# SCH_NFC-Card_2026-09-23.net
KiCad netlist of a schematic drawn in EasyEDA
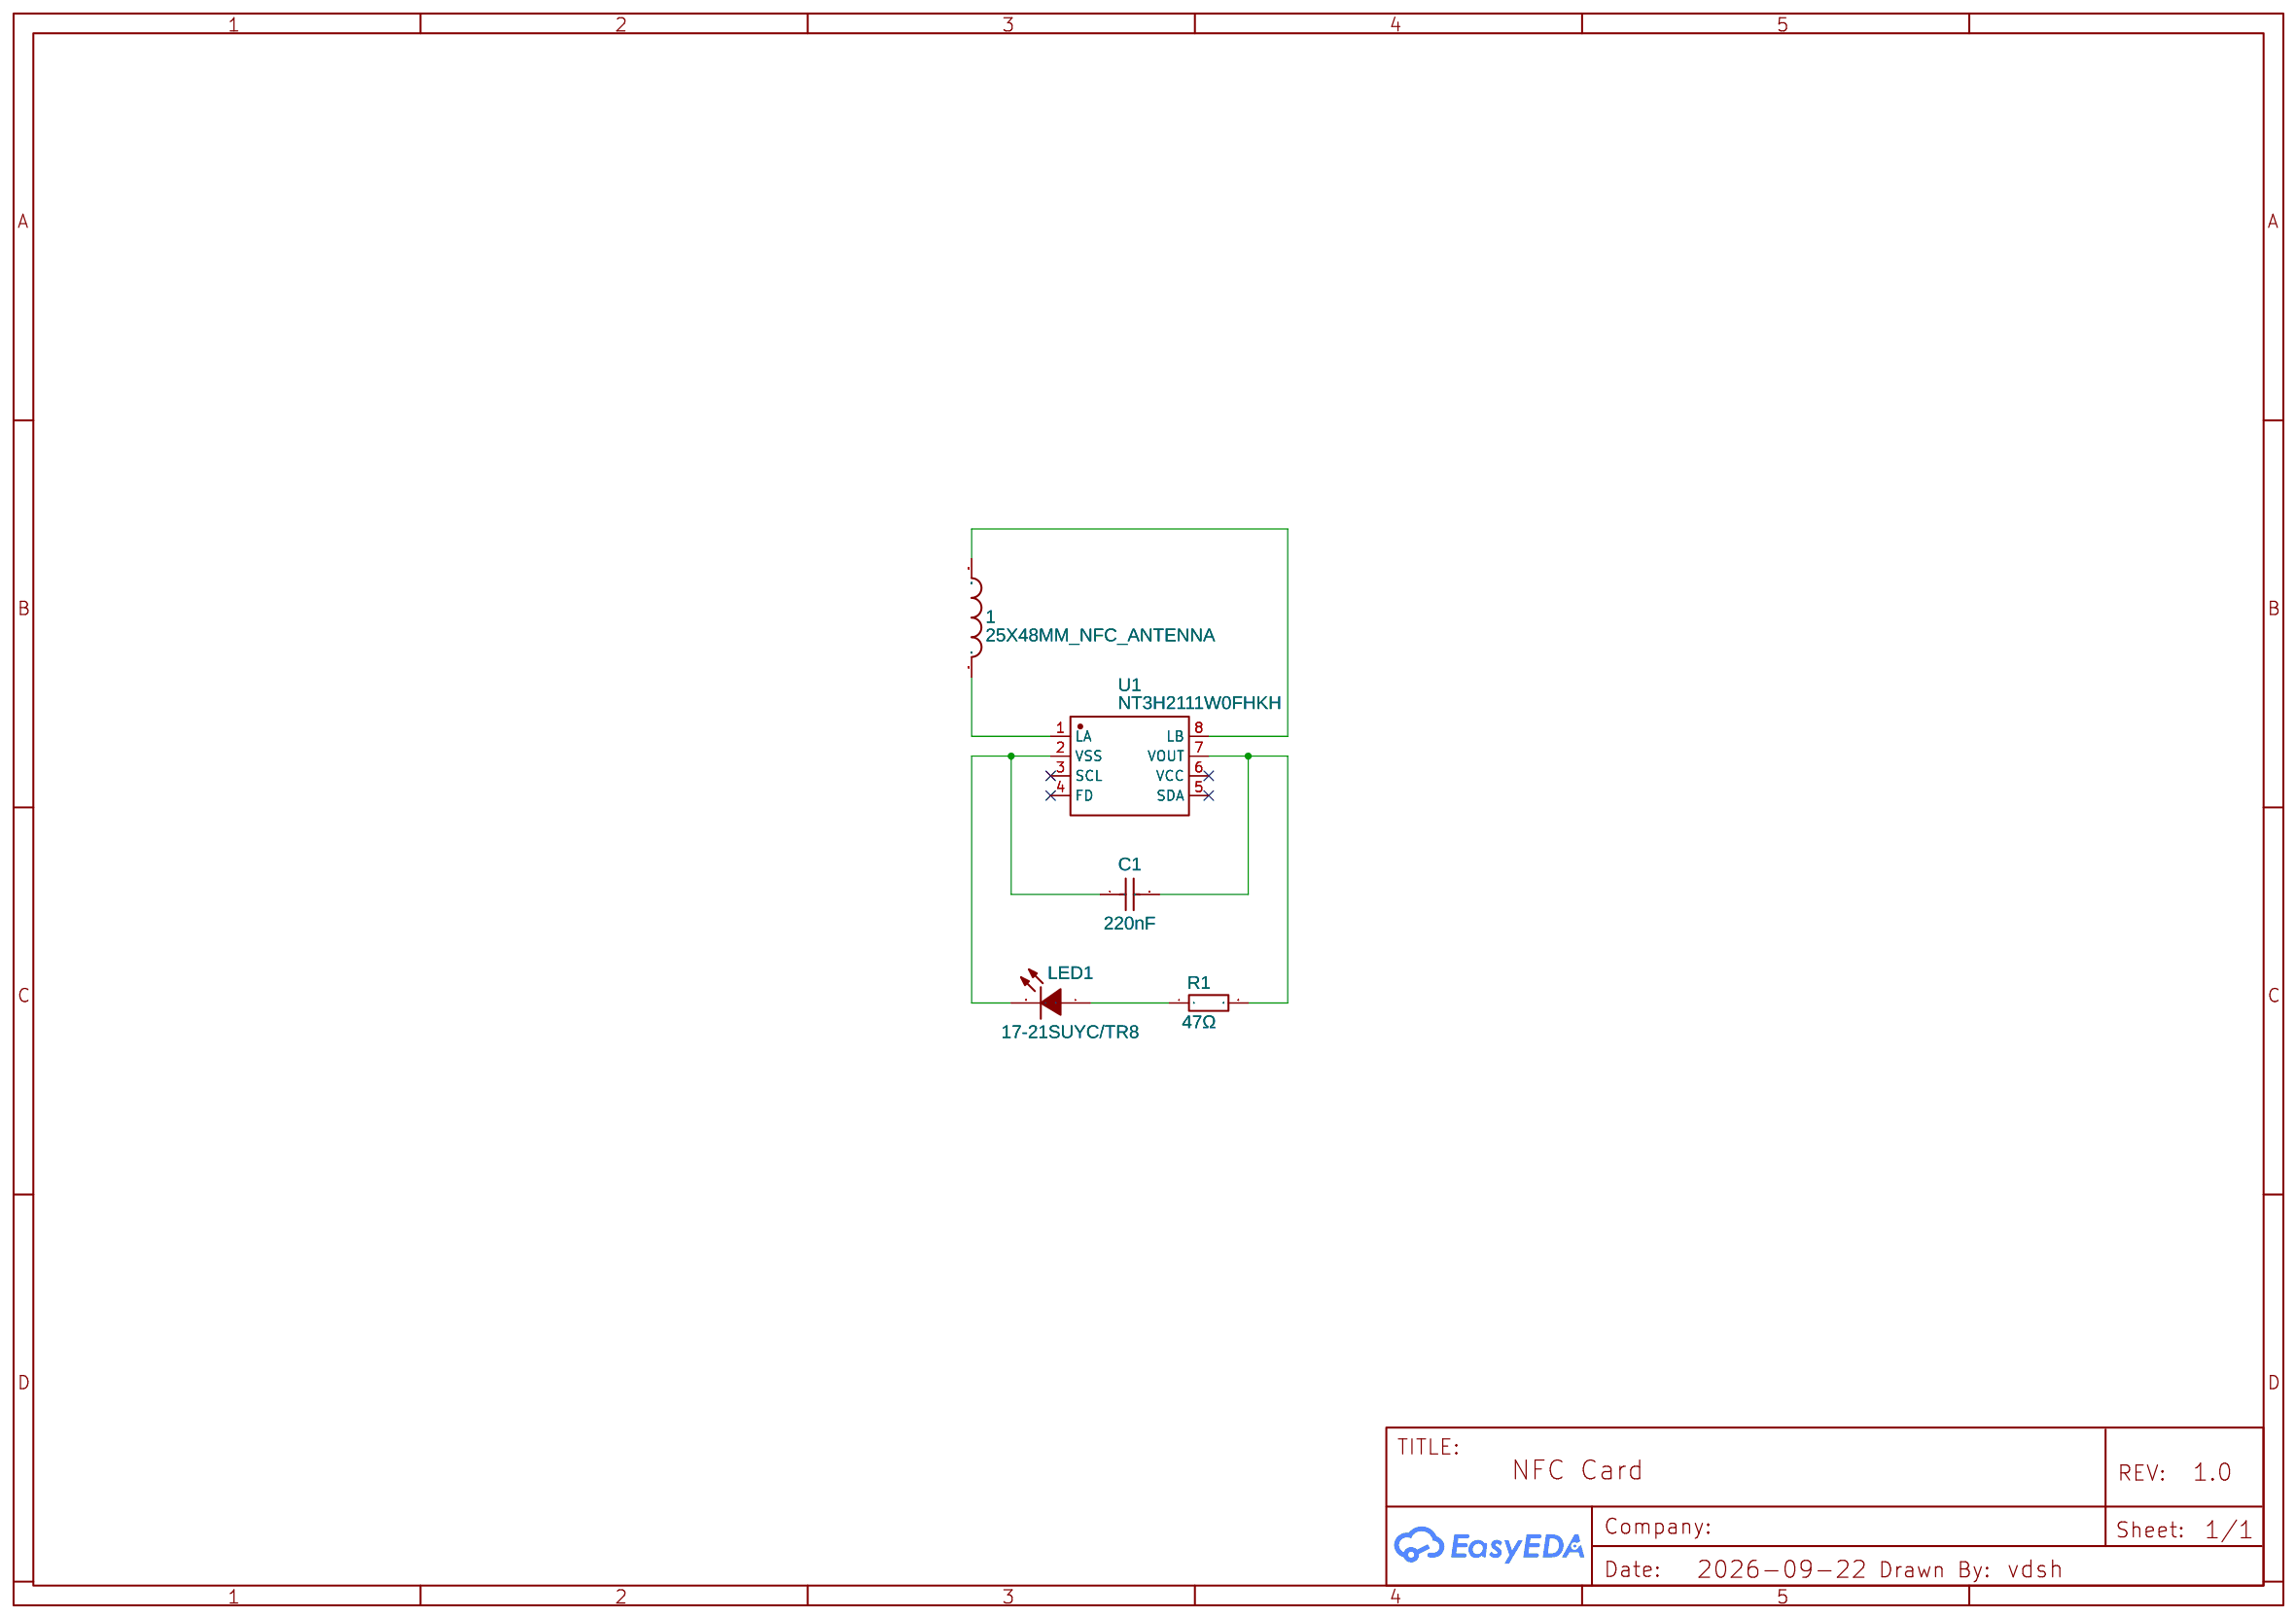
[diagram p0: schematic sheet]

(export (version "E")
  (design (tool "Eeschema 10.0.6"))
  (components
    (comp (ref "1") (value "25X48MM_NFC_ANTENNA") (libsource (lib "") (part "25X48MM_NFC_ANTENNA")))
    (comp (ref "C1")
      (value "220nF")
      (fields
        (field (name "Manufacturer Part") "CL10B224KA8NNNC")
        (field (name "Manufacturer") "SAMSUNG(三星)")
      )
      (libsource (lib "") (part "CL10B224KA8NNNC"))
    )
    (comp (ref "LED1")
      (value "17-21SUYC/TR8")
      (fields (field (name "Manufacturer Part") "KT-0805黄灯") (field (name "Manufacturer") "KENTO"))
      (libsource (lib "") (part "17-21SUYC/TR8"))
    )
    (comp (ref "R1")
      (value "47Ω")
      (fields
        (field (name "Manufacturer Part") "0603WAF470JT5E")
        (field (name "Manufacturer") "UNI-ROYAL(厚声)")
      )
      (libsource (lib "") (part "0603WAF470JT5E"))
    )
    (comp (ref "U1")
      (value "NT3H2111W0FHKH")
      (fields (field (name "Manufacturer") "NXP(恩智浦)"))
      (libsource (lib "") (part "NT3H2111W0FHKH"))
    )
  )
  (nets
    (net (code "1") (name "Net-(LED1-+)") (class "Default")
      (node (ref "LED1") (pin "1") (pinfunction "+_1") (pintype "unspecified"))
      (node (ref "R1") (pin "1") (pinfunction "1_1") (pintype "input"))
    )
    (net (code "2") (name "Net-(LED1--)") (class "Default")
      (node (ref "C1") (pin "1") (pinfunction "1_1") (pintype "input"))
      (node (ref "LED1") (pin "2") (pinfunction "-_2") (pintype "unspecified"))
      (node (ref "U1") (pin "2") (pinfunction "VSS_2") (pintype "unspecified"))
    )
    (net (code "3") (name "Net-(U1-LA)") (class "Default")
      (node (ref "1") (pin "P$2") (pinfunction "P$2_P$2") (pintype "bidirectional"))
      (node (ref "U1") (pin "1") (pinfunction "LA_1") (pintype "unspecified"))
    )
    (net (code "4") (name "Net-(U1-LB)") (class "Default")
      (node (ref "1") (pin "P$1") (pinfunction "P$1_P$1") (pintype "bidirectional"))
      (node (ref "U1") (pin "8") (pinfunction "LB_8") (pintype "unspecified"))
    )
    (net (code "5") (name "Net-(U1-VOUT)") (class "Default")
      (node (ref "C1") (pin "2") (pinfunction "2_2") (pintype "input"))
      (node (ref "R1") (pin "2") (pinfunction "2_2") (pintype "input"))
      (node (ref "U1") (pin "7") (pinfunction "VOUT_7") (pintype "unspecified"))
    )
    (net (code "6") (name "unconnected-(U1-FD-Pad4)") (class "Default")
      (node (ref "U1") (pin "4") (pinfunction "FD_4") (pintype "unspecified+no_connect"))
    )
    (net (code "7") (name "unconnected-(U1-SCL-Pad3)") (class "Default")
      (node (ref "U1") (pin "3") (pinfunction "SCL_3") (pintype "unspecified+no_connect"))
    )
    (net (code "8") (name "unconnected-(U1-SDA-Pad5)") (class "Default")
      (node (ref "U1") (pin "5") (pinfunction "SDA_5") (pintype "unspecified+no_connect"))
    )
    (net (code "9") (name "unconnected-(U1-VCC-Pad6)") (class "Default")
      (node (ref "U1") (pin "6") (pinfunction "VCC_6") (pintype "unspecified+no_connect"))
    )
  )
)
